# uc3843_flyback_converter.net
KiCad netlist of a schematic drawn in Altium Designer
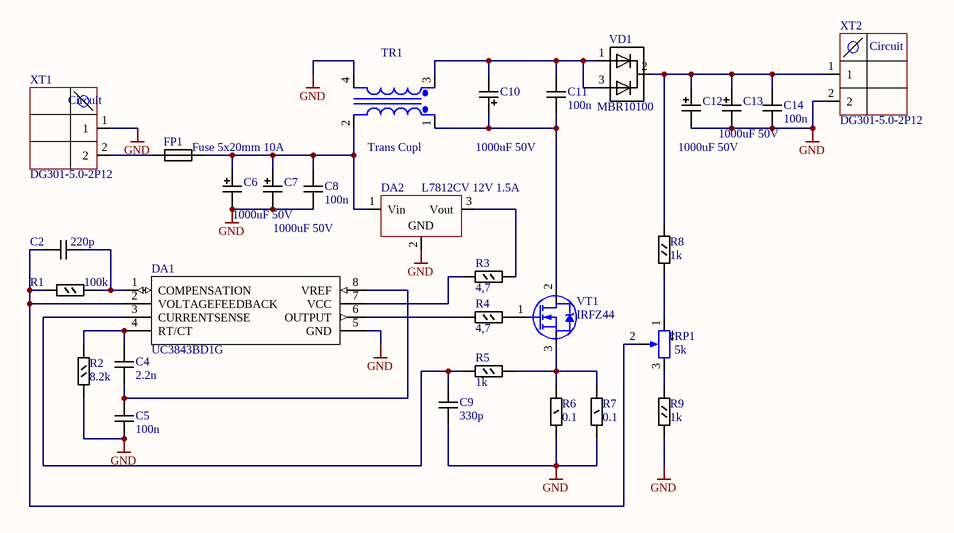
[diagram p0: uc3843 flyback converter.SchDoc]

(export (version "E")
  (design (tool "Eeschema 10.0.6"))
  (components
    (comp (ref "C2")
      (value "220p")
      (footprint "CAPC2012(0805)N")
      (fields (field (name "PART NUMBER") "CAPC2012(0805)"))
      (libsource (lib "SssAccesDatbase") (part "Cap"))
    )
    (comp (ref "C4")
      (value "2.2n")
      (footprint "CAPC2012(0805)N")
      (fields (field (name "PART NUMBER") "CAPC2012(0805)"))
      (libsource (lib "SssAccesDatbase") (part "Cap"))
    )
    (comp (ref "C5")
      (value "100n")
      (footprint "CAPC2012(0805)N")
      (fields (field (name "PART NUMBER") "CAPC2012(0805)"))
      (libsource (lib "SssAccesDatbase") (part "Cap"))
    )
    (comp (ref "C6")
      (value "1000uF 50V")
      (footprint "CAPPRD500W60D1300H2650")
      (description "CAP ALUM 1000UF 20% 50V RADIAL")
      (fields
        (field (name "PART NUMBER") "UVY1H102MHD")
        (field (name "DIGI-KEY PART NUMBER") "UVY1H102MHD-ND")
      )
      (libsource (lib "SssAccesDatbase") (part "Cap Pol1"))
    )
    (comp (ref "C7")
      (value "1000uF 50V")
      (footprint "CAPPRD500W60D1300H2650")
      (description "CAP ALUM 1000UF 20% 50V RADIAL")
      (fields
        (field (name "PART NUMBER") "UVY1H102MHD")
        (field (name "DIGI-KEY PART NUMBER") "UVY1H102MHD-ND")
      )
      (libsource (lib "SssAccesDatbase") (part "Cap Pol1"))
    )
    (comp (ref "C8")
      (value "100n")
      (footprint "CAPC2012(0805)N")
      (fields (field (name "PART NUMBER") "CAPC2012(0805)"))
      (libsource (lib "SssAccesDatbase") (part "Cap"))
    )
    (comp (ref "C9")
      (value "330p")
      (footprint "CAPC2012(0805)N")
      (fields (field (name "PART NUMBER") "CAPC2012(0805)"))
      (libsource (lib "SssAccesDatbase") (part "Cap"))
    )
    (comp (ref "C10")
      (value "1000uF 50V")
      (footprint "CAPPRD500W60D1300H2650")
      (description "CAP ALUM 1000UF 20% 50V RADIAL")
      (fields
        (field (name "PART NUMBER") "UVY1H102MHD")
        (field (name "DIGI-KEY PART NUMBER") "UVY1H102MHD-ND")
      )
      (libsource (lib "SssAccesDatbase") (part "Cap Pol1"))
    )
    (comp (ref "C11")
      (value "100n")
      (footprint "CAPC2012(0805)N")
      (fields (field (name "PART NUMBER") "CAPC2012(0805)"))
      (libsource (lib "SssAccesDatbase") (part "Cap"))
    )
    (comp (ref "C12")
      (value "1000uF 50V")
      (footprint "CAPPRD500W60D1300H2650")
      (description "CAP ALUM 1000UF 20% 50V RADIAL")
      (fields
        (field (name "PART NUMBER") "UVY1H102MHD")
        (field (name "DIGI-KEY PART NUMBER") "UVY1H102MHD-ND")
      )
      (libsource (lib "SssAccesDatbase") (part "Cap Pol1"))
    )
    (comp (ref "C13")
      (value "1000uF 50V")
      (footprint "CAPPRD500W60D1300H2650")
      (description "CAP ALUM 1000UF 20% 50V RADIAL")
      (fields
        (field (name "PART NUMBER") "UVY1H102MHD")
        (field (name "DIGI-KEY PART NUMBER") "UVY1H102MHD-ND")
      )
      (libsource (lib "SssAccesDatbase") (part "Cap Pol1"))
    )
    (comp (ref "C14")
      (value "100n")
      (footprint "CAPC2012(0805)N")
      (fields (field (name "PART NUMBER") "CAPC2012(0805)"))
      (libsource (lib "SssAccesDatbase") (part "Cap"))
    )
    (comp (ref "DA1")
      (value "UC3843BD1G")
      (footprint "SO-8_N")
      (description "Switching Controllers 52kHz 1A Current PWM w/96% Duty Cycle Max")
      (fields (field (name "MOUSER PART NUMBER") "863-UC3843BD1G"))
      (libsource (lib "SssAccesDatbase") (part "UC3843BD1G"))
    )
    (comp (ref "DA2")
      (value "L7812CV 12V 1.5A")
      (footprint "TO-220AB")
      (description "Linear Voltage Regulator IC  1 Output  1.5A TO-220AB")
      (fields (field (name "PART NUMBER") "L7812CV") (field (name "DIGI-KEY PART NUMBER") "497-1452-5-ND"))
      (libsource (lib "SssAccesDatbase") (part "VoltRegLiniar3pin"))
    )
    (comp (ref "FP1")
      (value "Fuse 5x20mm 10A")
      (footprint "FUSE_5X20MM")
      (fields (field (name "PART NUMBER") "Fuse 5x20mm"))
      (libsource (lib "SssAccesDatbase") (part "Fuse"))
    )
    (comp (ref "R1")
      (value "100k")
      (footprint "RESC2012(0805)N")
      (fields (field (name "PART NUMBER") "RESC2012(0805)"))
      (libsource (lib "") (part "Resistor 0,125W_1"))
    )
    (comp (ref "R2")
      (value "8.2k")
      (footprint "RESC2012(0805)N")
      (fields (field (name "PART NUMBER") "RESC2012(0805)"))
      (libsource (lib "SssAccesDatbase") (part "Resistor 0,125W"))
    )
    (comp (ref "R3")
      (value "4,7")
      (footprint "RESC2012(0805)N")
      (fields (field (name "PART NUMBER") "RESC2012(0805)"))
      (libsource (lib "") (part "Resistor 0,125W_1"))
    )
    (comp (ref "R4")
      (value "4,7")
      (footprint "RESC2012(0805)N")
      (fields (field (name "PART NUMBER") "RESC2012(0805)"))
      (libsource (lib "") (part "Resistor 0,125W_1"))
    )
    (comp (ref "R5")
      (value "1k")
      (footprint "RESC2012(0805)N")
      (fields (field (name "PART NUMBER") "RESC2012(0805)"))
      (libsource (lib "") (part "Resistor 0,125W_1"))
    )
    (comp (ref "R6")
      (value "0.1")
      (footprint "1206")
      (fields (field (name "PART NUMBER") "RESC3216(1206)"))
      (libsource (lib "SssAccesDatbase") (part "Resistor 0,25W"))
    )
    (comp (ref "R7")
      (value "0.1")
      (footprint "1206")
      (fields (field (name "PART NUMBER") "RESC3216(1206)"))
      (libsource (lib "SssAccesDatbase") (part "Resistor 0,25W"))
    )
    (comp (ref "R8")
      (value "1k")
      (footprint "RESC2012(0805)N")
      (fields (field (name "PART NUMBER") "RESC2012(0805)"))
      (libsource (lib "") (part "Resistor 0,125W_1"))
    )
    (comp (ref "R9")
      (value "1k")
      (footprint "RESC2012(0805)N")
      (fields (field (name "PART NUMBER") "RESC2012(0805)"))
      (libsource (lib "") (part "Resistor 0,125W_1"))
    )
    (comp (ref "RP1")
      (value "5k")
      (footprint "3296W")
      (fields (field (name "PART NUMBER") "Pot. 3296W") (field (name "MANUFACTURER PART NUMBER") "???"))
      (libsource (lib "SssAccesDatbase") (part "Pot"))
    )
    (comp (ref "TR1")
      (value "Trans Cupl")
      (footprint "Coilcraft-CMT1_3")
      (description "Coilcraft’s CMT toroid style common mode chokes")
      (fields (field (name "PART NUMBER") "Coilcraft-CMT1_3") (field (name "PUBLISHER") "Altium Limited"))
      (libsource (lib "SssAccesDatbase") (part "Trans Cupl"))
    )
    (comp (ref "VD1")
      (value "MBR10100")
      (footprint "TO-247AD")
      (description "Schottky Diodes & Rectifiers 60 Volt 40A Dual Common-Cathode")
      (fields (field (name "PART NUMBER") "MBR40H60PT-E3/45"))
      (libsource (lib "SssAccesDatbase") (part "Diode Dual Common Cathode"))
    )
    (comp (ref "VT1")
      (value "IRFZ44")
      (footprint "TO-220AB")
      (fields (field (name "PART NUMBER") "IRF630"))
      (libsource (lib "SssAccesDatbase") (part "N-Channel Mosfet"))
    )
    (comp (ref "XT1")
      (value "DG301-5.0-2P12")
      (footprint "DG301-5.0-2P12")
      (libsource (lib "") (part "XT-2_1"))
    )
    (comp (ref "XT2")
      (value "DG301-5.0-2P12")
      (footprint "DG301-5.0-2P12")
      (libsource (lib "SssAccesDatbase") (part "XT-2"))
    )
  )
  (nets
    (net (code "1") (name "GND") (class "Default")
      (node (ref "C12") (pin "2") (pinfunction "2_2") (pintype "passive"))
      (node (ref "C13") (pin "2") (pinfunction "2_2") (pintype "passive"))
      (node (ref "C14") (pin "1") (pinfunction "1_1") (pintype "passive"))
      (node (ref "C5") (pin "1") (pinfunction "1_1") (pintype "passive"))
      (node (ref "C6") (pin "2") (pinfunction "2_2") (pintype "passive"))
      (node (ref "C7") (pin "2") (pinfunction "2_2") (pintype "passive"))
      (node (ref "C8") (pin "1") (pinfunction "1_1") (pintype "passive"))
      (node (ref "C9") (pin "2") (pinfunction "2_2") (pintype "passive"))
      (node (ref "DA1") (pin "5") (pinfunction "GND_5") (pintype "power_in"))
      (node (ref "DA2") (pin "2") (pinfunction "GND_2") (pintype "passive"))
      (node (ref "R2") (pin "1") (pinfunction "1_1") (pintype "passive"))
      (node (ref "R6") (pin "1") (pinfunction "1_1") (pintype "passive"))
      (node (ref "R7") (pin "1") (pinfunction "1_1") (pintype "passive"))
      (node (ref "R9") (pin "2") (pinfunction "2_2") (pintype "passive"))
      (node (ref "TR1") (pin "4") (pinfunction "Sec-_4") (pintype "passive"))
      (node (ref "XT1") (pin "1") (pinfunction "1_1") (pintype "passive"))
      (node (ref "XT2") (pin "2") (pinfunction "2_2") (pintype "passive"))
    )
    (net (code "2") (name "Net-(C12-Pad1)") (class "Default")
      (node (ref "C12") (pin "1") (pinfunction "1_1") (pintype "passive"))
      (node (ref "C13") (pin "1") (pinfunction "1_1") (pintype "passive"))
      (node (ref "C14") (pin "2") (pinfunction "2_2") (pintype "passive"))
      (node (ref "R8") (pin "1") (pinfunction "1_1") (pintype "passive"))
      (node (ref "VD1") (pin "2") (pinfunction "2_2") (pintype "passive"))
      (node (ref "XT2") (pin "1") (pinfunction "1_1") (pintype "passive"))
    )
    (net (code "3") (name "Net-(DA1-COMPENSATION)") (class "Default")
      (node (ref "C2") (pin "2") (pinfunction "2_2") (pintype "passive"))
      (node (ref "DA1") (pin "1") (pinfunction "COMPENSATION_1") (pintype "bidirectional"))
      (node (ref "R1") (pin "1") (pinfunction "1_1") (pintype "passive"))
    )
    (net (code "4") (name "Net-(DA1-CURRENTSENSE)") (class "Default")
      (node (ref "C9") (pin "1") (pinfunction "1_1") (pintype "passive"))
      (node (ref "DA1") (pin "3") (pinfunction "CURRENTSENSE_3") (pintype "passive"))
      (node (ref "R5") (pin "2") (pinfunction "2_2") (pintype "passive"))
    )
    (net (code "5") (name "Net-(DA1-OUTPUT)") (class "Default")
      (node (ref "DA1") (pin "6") (pinfunction "OUTPUT_6") (pintype "output"))
      (node (ref "R4") (pin "2") (pinfunction "2_2") (pintype "passive"))
    )
    (net (code "6") (name "Net-(DA1-RT{slash}CT)") (class "Default")
      (node (ref "C4") (pin "2") (pinfunction "2_2") (pintype "passive"))
      (node (ref "DA1") (pin "4") (pinfunction "RT/CT_4") (pintype "passive"))
      (node (ref "R2") (pin "2") (pinfunction "2_2") (pintype "passive"))
    )
    (net (code "7") (name "Net-(DA1-VCC)") (class "Default")
      (node (ref "DA1") (pin "7") (pinfunction "VCC_7") (pintype "power_in"))
      (node (ref "R3") (pin "2") (pinfunction "2_2") (pintype "passive"))
    )
    (net (code "8") (name "Net-(DA1-VOLTAGEFEEDBACK)") (class "Default")
      (node (ref "C2") (pin "1") (pinfunction "1_1") (pintype "passive"))
      (node (ref "DA1") (pin "2") (pinfunction "VOLTAGEFEEDBACK_2") (pintype "passive"))
      (node (ref "R1") (pin "2") (pinfunction "2_2") (pintype "passive"))
      (node (ref "RP1") (pin "2") (pinfunction "BOT_2") (pintype "passive"))
    )
    (net (code "9") (name "Net-(DA1-VREF)") (class "Default")
      (node (ref "C4") (pin "1") (pinfunction "1_1") (pintype "passive"))
      (node (ref "C5") (pin "2") (pinfunction "2_2") (pintype "passive"))
      (node (ref "DA1") (pin "8") (pinfunction "VREF_8") (pintype "input"))
    )
    (net (code "10") (name "Net-(DA2-Vin)") (class "Default")
      (node (ref "C6") (pin "1") (pinfunction "1_1") (pintype "passive"))
      (node (ref "C7") (pin "1") (pinfunction "1_1") (pintype "passive"))
      (node (ref "C8") (pin "2") (pinfunction "2_2") (pintype "passive"))
      (node (ref "DA2") (pin "1") (pinfunction "Vin_1") (pintype "passive"))
      (node (ref "FP1") (pin "2") (pinfunction "2_2") (pintype "passive"))
      (node (ref "TR1") (pin "2") (pinfunction "Pri-_2") (pintype "passive"))
    )
    (net (code "11") (name "Net-(DA2-Vout)") (class "Default")
      (node (ref "DA2") (pin "3") (pinfunction "Vout_3") (pintype "passive"))
      (node (ref "R3") (pin "1") (pinfunction "1_1") (pintype "passive"))
    )
    (net (code "12") (name "Net-(FP1-Pad1)") (class "Default")
      (node (ref "FP1") (pin "1") (pinfunction "1_1") (pintype "passive"))
      (node (ref "XT1") (pin "2") (pinfunction "2_2") (pintype "passive"))
    )
    (net (code "13") (name "Net-(RP1-TAP)") (class "Default")
      (node (ref "R9") (pin "1") (pinfunction "1_1") (pintype "passive"))
      (node (ref "RP1") (pin "3") (pinfunction "TAP_3") (pintype "passive"))
    )
    (net (code "14") (name "Net-(RP1-TOP)") (class "Default")
      (node (ref "R8") (pin "2") (pinfunction "2_2") (pintype "passive"))
      (node (ref "RP1") (pin "1") (pinfunction "TOP_1") (pintype "passive"))
    )
    (net (code "15") (name "Net-(TR1-Pri+)") (class "Default")
      (node (ref "C10") (pin "1") (pinfunction "1_1") (pintype "passive"))
      (node (ref "C11") (pin "2") (pinfunction "2_2") (pintype "passive"))
      (node (ref "TR1") (pin "1") (pinfunction "Pri+_1") (pintype "passive"))
      (node (ref "VT1") (pin "2") (pinfunction "D_2") (pintype "passive"))
    )
    (net (code "16") (name "Net-(TR1-Sec+)") (class "Default")
      (node (ref "C10") (pin "2") (pinfunction "2_2") (pintype "passive"))
      (node (ref "C11") (pin "1") (pinfunction "1_1") (pintype "passive"))
      (node (ref "TR1") (pin "3") (pinfunction "Sec+_3") (pintype "passive"))
      (node (ref "VD1") (pin "1") (pinfunction "1_1") (pintype "passive"))
      (node (ref "VD1") (pin "3") (pinfunction "3_3") (pintype "passive"))
    )
    (net (code "17") (name "Net-(VT1-G)") (class "Default")
      (node (ref "R4") (pin "1") (pinfunction "1_1") (pintype "passive"))
      (node (ref "VT1") (pin "1") (pinfunction "G_1") (pintype "passive"))
    )
    (net (code "18") (name "Net-(VT1-S)") (class "Default")
      (node (ref "R5") (pin "1") (pinfunction "1_1") (pintype "passive"))
      (node (ref "R6") (pin "2") (pinfunction "2_2") (pintype "passive"))
      (node (ref "R7") (pin "2") (pinfunction "2_2") (pintype "passive"))
      (node (ref "VT1") (pin "3") (pinfunction "S_3") (pintype "passive"))
    )
  )
)
